# Sheet2.net
KiCad netlist of a schematic drawn in Altium Designer
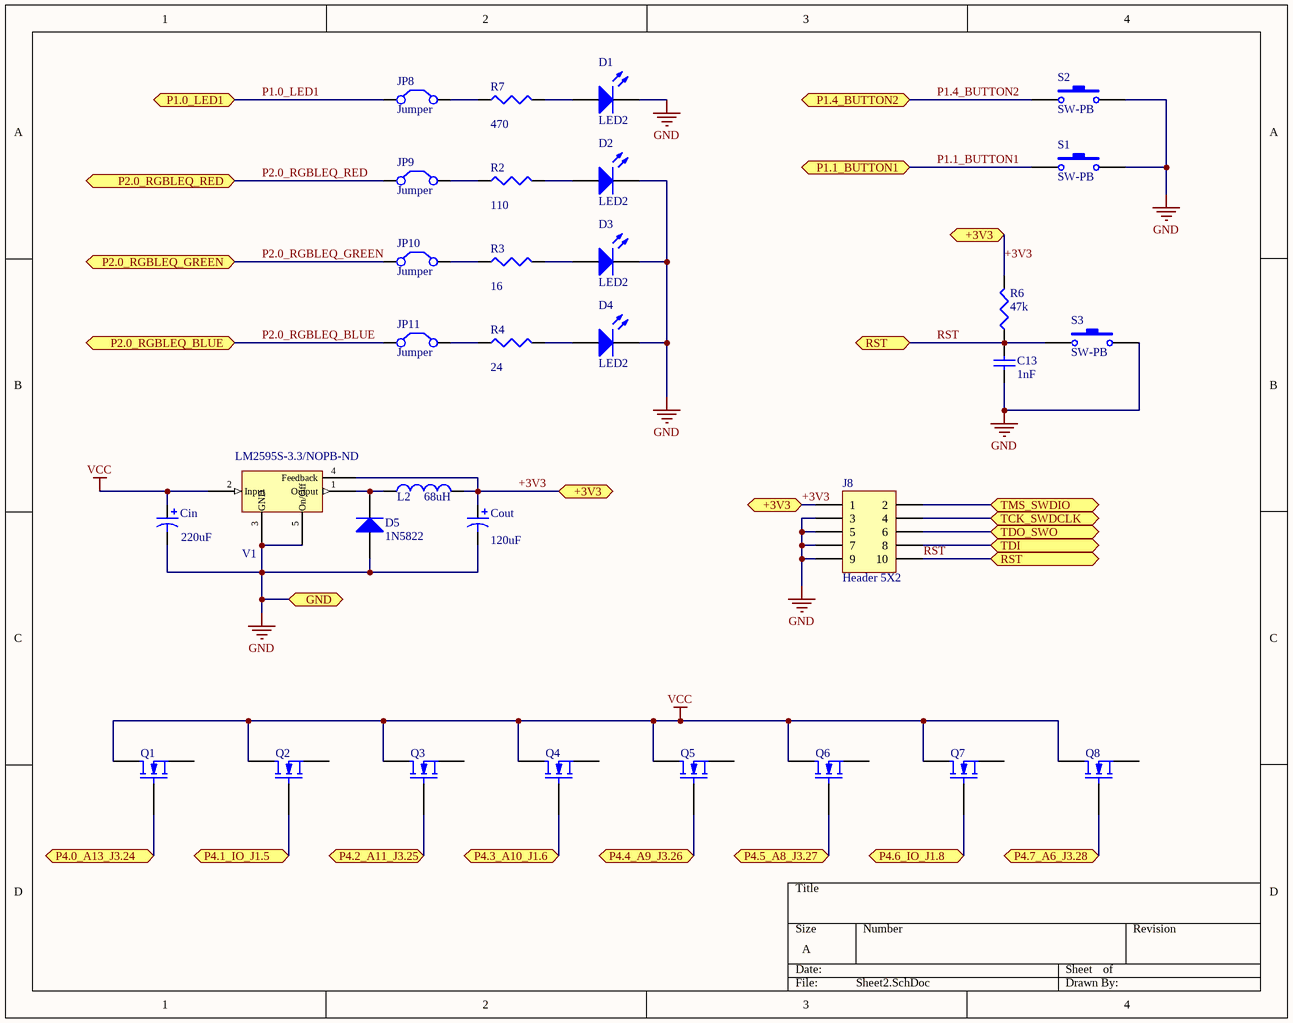
[diagram p0: Sheet2.SchDoc]

(export (version "E")
  (design (tool "Eeschema 10.0.6"))
  (components
    (comp (ref "C13")
      (value "1nF")
      (footprint "0402")
      (description "Capacitor (Semiconductor SIM Model)")
      (fields (field (name "Comment") "Cap Semi") (field (name "PUBLISHER") "Altium Limited"))
      (libsource (lib "Miscellaneous Devices") (part "Cap Semi"))
    )
    (comp (ref "Cin")
      (value "220uF")
      (footprint "C0805")
      (description "Polarized Capacitor (Surface Mount)")
      (fields (field (name "Comment") "Cap Pol3") (field (name "PUBLISHER") "Altium Limited"))
      (libsource (lib "Miscellaneous Devices") (part "Cap Pol3"))
    )
    (comp (ref "Cout")
      (value "120uF")
      (footprint "C0805")
      (description "Polarized Capacitor (Surface Mount)")
      (fields (field (name "Comment") "Cap Pol3") (field (name "PUBLISHER") "Altium Limited"))
      (libsource (lib "Miscellaneous Devices") (part "Cap Pol3"))
    )
    (comp (ref "D1")
      (value "LED2")
      (footprint "3.2X1.6X1.1")
      (description "Typical RED, GREEN, YELLOW, AMBER GaAs LED")
      (fields (field (name "PUBLISHER") "Altium Limited"))
      (libsource (lib "Miscellaneous Devices") (part "LED2"))
    )
    (comp (ref "D2")
      (value "LED2")
      (footprint "3.2X1.6X1.1")
      (description "Typical RED, GREEN, YELLOW, AMBER GaAs LED")
      (fields (field (name "PUBLISHER") "Altium Limited"))
      (libsource (lib "Miscellaneous Devices") (part "LED2"))
    )
    (comp (ref "D3")
      (value "LED2")
      (footprint "3.2X1.6X1.1")
      (description "Typical RED, GREEN, YELLOW, AMBER GaAs LED")
      (fields (field (name "PUBLISHER") "Altium Limited"))
      (libsource (lib "Miscellaneous Devices") (part "LED2"))
    )
    (comp (ref "D4")
      (value "LED2")
      (footprint "3.2X1.6X1.1")
      (description "Typical RED, GREEN, YELLOW, AMBER GaAs LED")
      (fields (field (name "PUBLISHER") "Altium Limited"))
      (libsource (lib "Miscellaneous Devices") (part "LED2"))
    )
    (comp (ref "D5")
      (value "1N5822")
      (footprint "DO-201AD")
      (description "3 Amp Medium Power Silicon Rectifier Diode")
      (fields (field (name "PUBLISHER") "Altium Limited"))
      (libsource (lib "Miscellaneous Devices") (part "Diode 1N5408"))
    )
    (comp (ref "J8")
      (value "Header 5X2")
      (footprint "HDR2X5")
      (description "Header, 5-Pin, Dual row")
      (fields (field (name "PUBLISHER") "Altium Limited"))
      (libsource (lib "Miscellaneous Connectors") (part "Header 5X2"))
    )
    (comp (ref "JP8")
      (value "Jumper")
      (footprint "RAD-0.2")
      (description "Jumper Wire")
      (fields (field (name "PUBLISHER") "Altium Limited"))
      (libsource (lib "Miscellaneous Devices") (part "Jumper"))
    )
    (comp (ref "JP9")
      (value "Jumper")
      (footprint "RAD-0.2")
      (description "Jumper Wire")
      (fields (field (name "PUBLISHER") "Altium Limited"))
      (libsource (lib "Miscellaneous Devices") (part "Jumper"))
    )
    (comp (ref "JP10")
      (value "Jumper")
      (footprint "RAD-0.2")
      (description "Jumper Wire")
      (fields (field (name "PUBLISHER") "Altium Limited"))
      (libsource (lib "Miscellaneous Devices") (part "Jumper"))
    )
    (comp (ref "JP11")
      (value "Jumper")
      (footprint "RAD-0.2")
      (description "Jumper Wire")
      (fields (field (name "PUBLISHER") "Altium Limited"))
      (libsource (lib "Miscellaneous Devices") (part "Jumper"))
    )
    (comp (ref "L2")
      (value "68uH")
      (footprint "0402-A")
      (description "Inductor")
      (fields (field (name "PUBLISHER") "Altium Limited"))
      (libsource (lib "Miscellaneous Devices") (part "Inductor"))
    )
    (comp (ref "Q1")
      (value "MOSFET-N")
      (footprint "SiUD41ED")
      (libsource (lib "actuatorBoard") (part "SiUD41ED"))
    )
    (comp (ref "Q2")
      (value "MOSFET-N")
      (footprint "SiUD41ED")
      (libsource (lib "actuatorBoard") (part "SiUD41ED"))
    )
    (comp (ref "Q3")
      (value "MOSFET-N")
      (footprint "SiUD41ED")
      (libsource (lib "actuatorBoard") (part "SiUD41ED"))
    )
    (comp (ref "Q4")
      (value "MOSFET-N")
      (footprint "SiUD41ED")
      (libsource (lib "actuatorBoard") (part "SiUD41ED"))
    )
    (comp (ref "Q5")
      (value "MOSFET-N")
      (footprint "SiUD41ED")
      (libsource (lib "actuatorBoard") (part "SiUD41ED"))
    )
    (comp (ref "Q6")
      (value "MOSFET-N")
      (footprint "SiUD41ED")
      (libsource (lib "actuatorBoard") (part "SiUD41ED"))
    )
    (comp (ref "Q7")
      (value "MOSFET-N")
      (footprint "SiUD41ED")
      (libsource (lib "actuatorBoard") (part "SiUD41ED"))
    )
    (comp (ref "Q8")
      (value "MOSFET-N")
      (footprint "SiUD41ED")
      (libsource (lib "actuatorBoard") (part "SiUD41ED"))
    )
    (comp (ref "R2")
      (value "110")
      (footprint "J1-0603")
      (description "Resistor")
      (fields (field (name "Comment") "Res3") (field (name "PUBLISHER") "Altium Limited"))
      (libsource (lib "Miscellaneous Devices") (part "Res3"))
    )
    (comp (ref "R3")
      (value "16")
      (footprint "J1-0603")
      (description "Resistor")
      (fields (field (name "Comment") "Res3") (field (name "PUBLISHER") "Altium Limited"))
      (libsource (lib "Miscellaneous Devices") (part "Res3"))
    )
    (comp (ref "R4")
      (value "24")
      (footprint "J1-0603")
      (description "Resistor")
      (fields (field (name "Comment") "Res3") (field (name "PUBLISHER") "Altium Limited"))
      (libsource (lib "Miscellaneous Devices") (part "Res3"))
    )
    (comp (ref "R6")
      (value "47k")
      (footprint "J1-0603")
      (description "Resistor")
      (fields (field (name "Comment") "Res3") (field (name "PUBLISHER") "Altium Limited"))
      (libsource (lib "Miscellaneous Devices") (part "Res3"))
    )
    (comp (ref "R7")
      (value "470")
      (footprint "J1-0603")
      (description "Resistor")
      (fields (field (name "Comment") "Res3") (field (name "PUBLISHER") "Altium Limited"))
      (libsource (lib "Miscellaneous Devices") (part "Res3"))
    )
    (comp (ref "S1")
      (value "SW-PB")
      (footprint "SPST-2")
      (description "Switch")
      (fields (field (name "PUBLISHER") "Altium Limited"))
      (libsource (lib "Miscellaneous Devices") (part "SW-PB"))
    )
    (comp (ref "S2")
      (value "SW-PB")
      (footprint "SPST-2")
      (description "Switch")
      (fields (field (name "PUBLISHER") "Altium Limited"))
      (libsource (lib "Miscellaneous Devices") (part "SW-PB"))
    )
    (comp (ref "S3")
      (value "SW-PB")
      (footprint "SPST-2")
      (description "Switch")
      (fields (field (name "PUBLISHER") "Altium Limited"))
      (libsource (lib "Miscellaneous Devices") (part "SW-PB"))
    )
    (comp (ref "V1")
      (value "LM2595S-3.3/NOPB-ND")
      (footprint "LM2595S-3.3/NOPB-ND")
      (libsource (lib "actuatorBoard") (part "LM2595S-3.3/NOPB-ND"))
    )
  )
  (nets
    (net (code "1") (name "/+3V3") (class "Default")
      (node (ref "Cout") (pin "1") (pinfunction "1_1") (pintype "passive"))
      (node (ref "J8") (pin "1") (pinfunction "1_1") (pintype "passive"))
      (node (ref "L2") (pin "2") (pinfunction "2_2") (pintype "passive"))
      (node (ref "R6") (pin "2") (pinfunction "2_2") (pintype "passive"))
      (node (ref "V1") (pin "4") (pinfunction "Feedback_4") (pintype "passive"))
    )
    (net (code "2") (name "/P1.0_LED1") (class "Default")
      (node (ref "JP8") (pin "1") (pinfunction "C1_1") (pintype "passive"))
    )
    (net (code "3") (name "/P1.1_BUTTON1") (class "Default")
      (node (ref "S1") (pin "1") (pinfunction "1_1") (pintype "passive"))
    )
    (net (code "4") (name "/P1.4_BUTTON2") (class "Default")
      (node (ref "S2") (pin "1") (pinfunction "1_1") (pintype "passive"))
    )
    (net (code "5") (name "/P2.0_RGBLEQ_BLUE") (class "Default")
      (node (ref "JP11") (pin "1") (pinfunction "C1_1") (pintype "passive"))
    )
    (net (code "6") (name "/P2.0_RGBLEQ_GREEN") (class "Default")
      (node (ref "JP10") (pin "1") (pinfunction "C1_1") (pintype "passive"))
    )
    (net (code "7") (name "/P2.0_RGBLEQ_RED") (class "Default")
      (node (ref "JP9") (pin "1") (pinfunction "C1_1") (pintype "passive"))
    )
    (net (code "8") (name "/P4.0_A13_J3.24") (class "Default")
      (node (ref "Q1") (pin "1") (pinfunction "1_1") (pintype "passive"))
    )
    (net (code "9") (name "/P4.1_IO_J1.5") (class "Default")
      (node (ref "Q2") (pin "1") (pinfunction "1_1") (pintype "passive"))
    )
    (net (code "10") (name "/P4.2_A11_J3.25") (class "Default")
      (node (ref "Q3") (pin "1") (pinfunction "1_1") (pintype "passive"))
    )
    (net (code "11") (name "/P4.3_A10_J1.6") (class "Default")
      (node (ref "Q4") (pin "1") (pinfunction "1_1") (pintype "passive"))
    )
    (net (code "12") (name "/P4.4_A9_J3.26") (class "Default")
      (node (ref "Q5") (pin "1") (pinfunction "1_1") (pintype "passive"))
    )
    (net (code "13") (name "/P4.5_A8_J3.27") (class "Default")
      (node (ref "Q6") (pin "1") (pinfunction "1_1") (pintype "passive"))
    )
    (net (code "14") (name "/P4.6_IO_J1.8") (class "Default")
      (node (ref "Q7") (pin "1") (pinfunction "1_1") (pintype "passive"))
    )
    (net (code "15") (name "/P4.7_A6_J3.28") (class "Default")
      (node (ref "Q8") (pin "1") (pinfunction "1_1") (pintype "passive"))
    )
    (net (code "16") (name "/RST") (class "Default")
      (node (ref "C13") (pin "2") (pinfunction "2_2") (pintype "passive"))
      (node (ref "J8") (pin "10") (pinfunction "10_10") (pintype "passive"))
      (node (ref "R6") (pin "1") (pinfunction "1_1") (pintype "passive"))
      (node (ref "S3") (pin "1") (pinfunction "1_1") (pintype "passive"))
    )
    (net (code "17") (name "/TCK_SWDCLK") (class "Default")
      (node (ref "J8") (pin "4") (pinfunction "4_4") (pintype "passive"))
    )
    (net (code "18") (name "/TDI") (class "Default")
      (node (ref "J8") (pin "8") (pinfunction "8_8") (pintype "passive"))
    )
    (net (code "19") (name "/TDO_SWO") (class "Default")
      (node (ref "J8") (pin "6") (pinfunction "6_6") (pintype "passive"))
    )
    (net (code "20") (name "/TMS_SWDIO") (class "Default")
      (node (ref "J8") (pin "2") (pinfunction "2_2") (pintype "passive"))
    )
    (net (code "21") (name "GND") (class "Default")
      (node (ref "C13") (pin "1") (pinfunction "1_1") (pintype "passive"))
      (node (ref "Cin") (pin "2") (pinfunction "2_2") (pintype "passive"))
      (node (ref "Cout") (pin "2") (pinfunction "2_2") (pintype "passive"))
      (node (ref "D1") (pin "2") (pinfunction "K_2") (pintype "passive"))
      (node (ref "D2") (pin "2") (pinfunction "K_2") (pintype "passive"))
      (node (ref "D3") (pin "2") (pinfunction "K_2") (pintype "passive"))
      (node (ref "D4") (pin "2") (pinfunction "K_2") (pintype "passive"))
      (node (ref "D5") (pin "1") (pinfunction "A_1") (pintype "passive"))
      (node (ref "J8") (pin "3") (pinfunction "3_3") (pintype "passive"))
      (node (ref "J8") (pin "5") (pinfunction "5_5") (pintype "passive"))
      (node (ref "J8") (pin "7") (pinfunction "7_7") (pintype "passive"))
      (node (ref "J8") (pin "9") (pinfunction "9_9") (pintype "passive"))
      (node (ref "S1") (pin "2") (pinfunction "2_2") (pintype "passive"))
      (node (ref "S2") (pin "2") (pinfunction "2_2") (pintype "passive"))
      (node (ref "S3") (pin "2") (pinfunction "2_2") (pintype "passive"))
      (node (ref "V1") (pin "3") (pinfunction "GND_3") (pintype "passive"))
      (node (ref "V1") (pin "5") (pinfunction "On/Off_5") (pintype "passive"))
    )
    (net (code "22") (name "Net-(D1-A)") (class "Default")
      (node (ref "D1") (pin "1") (pinfunction "A_1") (pintype "passive"))
      (node (ref "R7") (pin "2") (pinfunction "2_2") (pintype "passive"))
    )
    (net (code "23") (name "Net-(D2-A)") (class "Default")
      (node (ref "D2") (pin "1") (pinfunction "A_1") (pintype "passive"))
      (node (ref "R2") (pin "2") (pinfunction "2_2") (pintype "passive"))
    )
    (net (code "24") (name "Net-(D3-A)") (class "Default")
      (node (ref "D3") (pin "1") (pinfunction "A_1") (pintype "passive"))
      (node (ref "R3") (pin "2") (pinfunction "2_2") (pintype "passive"))
    )
    (net (code "25") (name "Net-(D4-A)") (class "Default")
      (node (ref "D4") (pin "1") (pinfunction "A_1") (pintype "passive"))
      (node (ref "R4") (pin "2") (pinfunction "2_2") (pintype "passive"))
    )
    (net (code "26") (name "Net-(D5-K)") (class "Default")
      (node (ref "D5") (pin "2") (pinfunction "K_2") (pintype "passive"))
      (node (ref "L2") (pin "1") (pinfunction "1_1") (pintype "passive"))
      (node (ref "V1") (pin "1") (pinfunction "Output_1") (pintype "output"))
    )
    (net (code "27") (name "Net-(JP8-C2)") (class "Default")
      (node (ref "JP8") (pin "2") (pinfunction "C2_2") (pintype "passive"))
      (node (ref "R7") (pin "1") (pinfunction "1_1") (pintype "passive"))
    )
    (net (code "28") (name "Net-(JP9-C2)") (class "Default")
      (node (ref "JP9") (pin "2") (pinfunction "C2_2") (pintype "passive"))
      (node (ref "R2") (pin "1") (pinfunction "1_1") (pintype "passive"))
    )
    (net (code "29") (name "Net-(JP10-C2)") (class "Default")
      (node (ref "JP10") (pin "2") (pinfunction "C2_2") (pintype "passive"))
      (node (ref "R3") (pin "1") (pinfunction "1_1") (pintype "passive"))
    )
    (net (code "30") (name "Net-(JP11-C2)") (class "Default")
      (node (ref "JP11") (pin "2") (pinfunction "C2_2") (pintype "passive"))
      (node (ref "R4") (pin "1") (pinfunction "1_1") (pintype "passive"))
    )
    (net (code "31") (name "VCC") (class "Default")
      (node (ref "Cin") (pin "1") (pinfunction "1_1") (pintype "passive"))
      (node (ref "Q1") (pin "3") (pinfunction "3_3") (pintype "passive"))
      (node (ref "Q2") (pin "3") (pinfunction "3_3") (pintype "passive"))
      (node (ref "Q3") (pin "3") (pinfunction "3_3") (pintype "passive"))
      (node (ref "Q4") (pin "3") (pinfunction "3_3") (pintype "passive"))
      (node (ref "Q5") (pin "3") (pinfunction "3_3") (pintype "passive"))
      (node (ref "Q6") (pin "3") (pinfunction "3_3") (pintype "passive"))
      (node (ref "Q7") (pin "3") (pinfunction "3_3") (pintype "passive"))
      (node (ref "Q8") (pin "3") (pinfunction "3_3") (pintype "passive"))
      (node (ref "V1") (pin "2") (pinfunction "Input_2") (pintype "input"))
    )
    (net (code "32") (name "unconnected-(Q1-Pad2)") (class "Default")
      (node (ref "Q1") (pin "2") (pinfunction "2_2") (pintype "passive"))
    )
    (net (code "33") (name "unconnected-(Q2-Pad2)") (class "Default")
      (node (ref "Q2") (pin "2") (pinfunction "2_2") (pintype "passive"))
    )
    (net (code "34") (name "unconnected-(Q3-Pad2)") (class "Default")
      (node (ref "Q3") (pin "2") (pinfunction "2_2") (pintype "passive"))
    )
    (net (code "35") (name "unconnected-(Q4-Pad2)") (class "Default")
      (node (ref "Q4") (pin "2") (pinfunction "2_2") (pintype "passive"))
    )
    (net (code "36") (name "unconnected-(Q5-Pad2)") (class "Default")
      (node (ref "Q5") (pin "2") (pinfunction "2_2") (pintype "passive"))
    )
    (net (code "37") (name "unconnected-(Q6-Pad2)") (class "Default")
      (node (ref "Q6") (pin "2") (pinfunction "2_2") (pintype "passive"))
    )
    (net (code "38") (name "unconnected-(Q7-Pad2)") (class "Default")
      (node (ref "Q7") (pin "2") (pinfunction "2_2") (pintype "passive"))
    )
    (net (code "39") (name "unconnected-(Q8-Pad2)") (class "Default")
      (node (ref "Q8") (pin "2") (pinfunction "2_2") (pintype "passive"))
    )
  )
)
